# CAN.net
KiCad netlist of a schematic drawn in Altium Designer
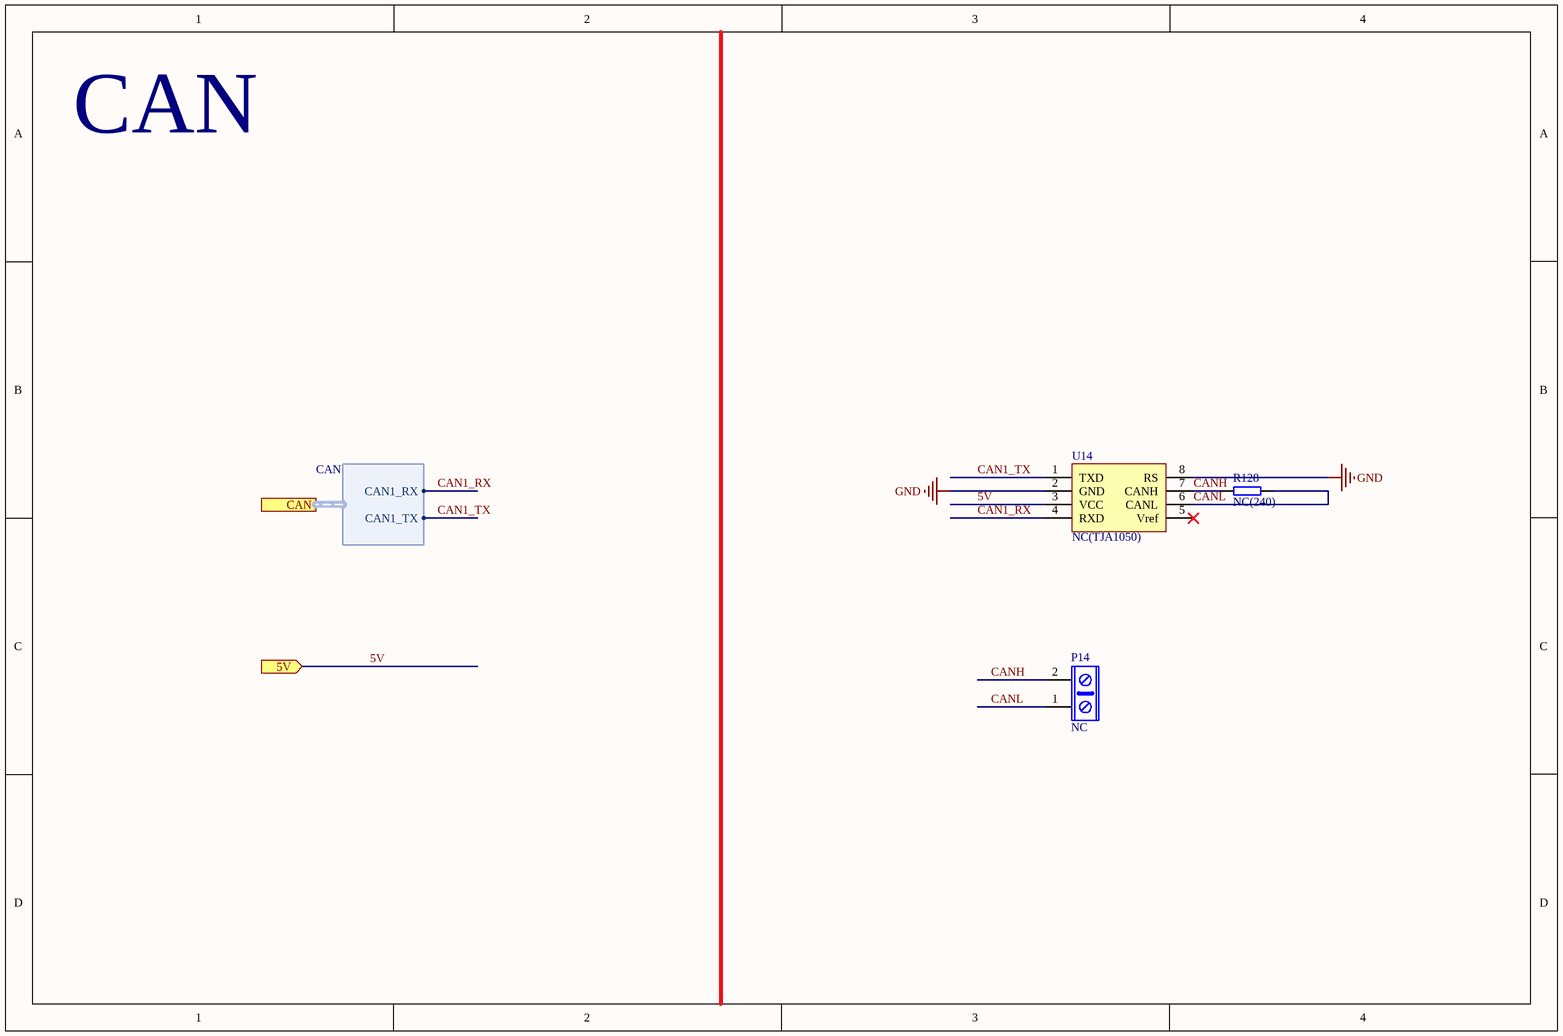
[diagram p0: CAN.SchDoc]

(export (version "E")
  (design (tool "Eeschema 10.0.6"))
  (components
    (comp (ref "P14")
      (value "NC")
      (footprint "PORT2-5.08MM")
      (description "接线端子 2脚")
      (libsource (lib "wch_sch_others") (part "接线端子"))
    )
    (comp (ref "R128") (value "NC(240)") (footprint "0402") (libsource (lib "wch_sch_others") (part "RES")))
    (comp (ref "U14")
      (value "NC(TJA1050)")
      (footprint "SOP8")
      (description "High speed CAN transceiver")
      (libsource (lib "wch_sch_others") (part "TJA1050"))
    )
  )
  (nets
    (net (code "2") (name "/5V") (class "Default")
      (node (ref "U14") (pin "3") (pinfunction "VCC_3") (pintype "passive"))
    )
    (net (code "3") (name "/CAN1_RX") (class "Default")
      (node (ref "U14") (pin "4") (pinfunction "RXD_4") (pintype "passive"))
    )
    (net (code "4") (name "/CAN1_TX") (class "Default")
      (node (ref "U14") (pin "1") (pinfunction "TXD_1") (pintype "passive"))
    )
    (net (code "5") (name "/CANH") (class "Default")
      (node (ref "P14") (pin "2") (pinfunction "2_2") (pintype "passive"))
      (node (ref "R128") (pin "1") (pintype "passive"))
      (node (ref "U14") (pin "7") (pinfunction "CANH_7") (pintype "passive"))
    )
    (net (code "6") (name "/CANL") (class "Default")
      (node (ref "P14") (pin "1") (pinfunction "1_1") (pintype "passive"))
      (node (ref "R128") (pin "2") (pintype "passive"))
      (node (ref "U14") (pin "6") (pinfunction "CANL_6") (pintype "passive"))
    )
    (net (code "8") (name "GND") (class "Default")
      (node (ref "U14") (pin "2") (pinfunction "GND_2") (pintype "passive"))
      (node (ref "U14") (pin "8") (pinfunction "RS_8") (pintype "passive"))
    )
    (net (code "9") (name "unconnected-(U14-Vref-Pad5)") (class "Default")
      (node (ref "U14") (pin "5") (pinfunction "Vref_5") (pintype "passive+no_connect"))
    )
  )
)
